# amp-PA-UHF-TQP7M9106.net
KiCad netlist of a schematic drawn in EAGLE
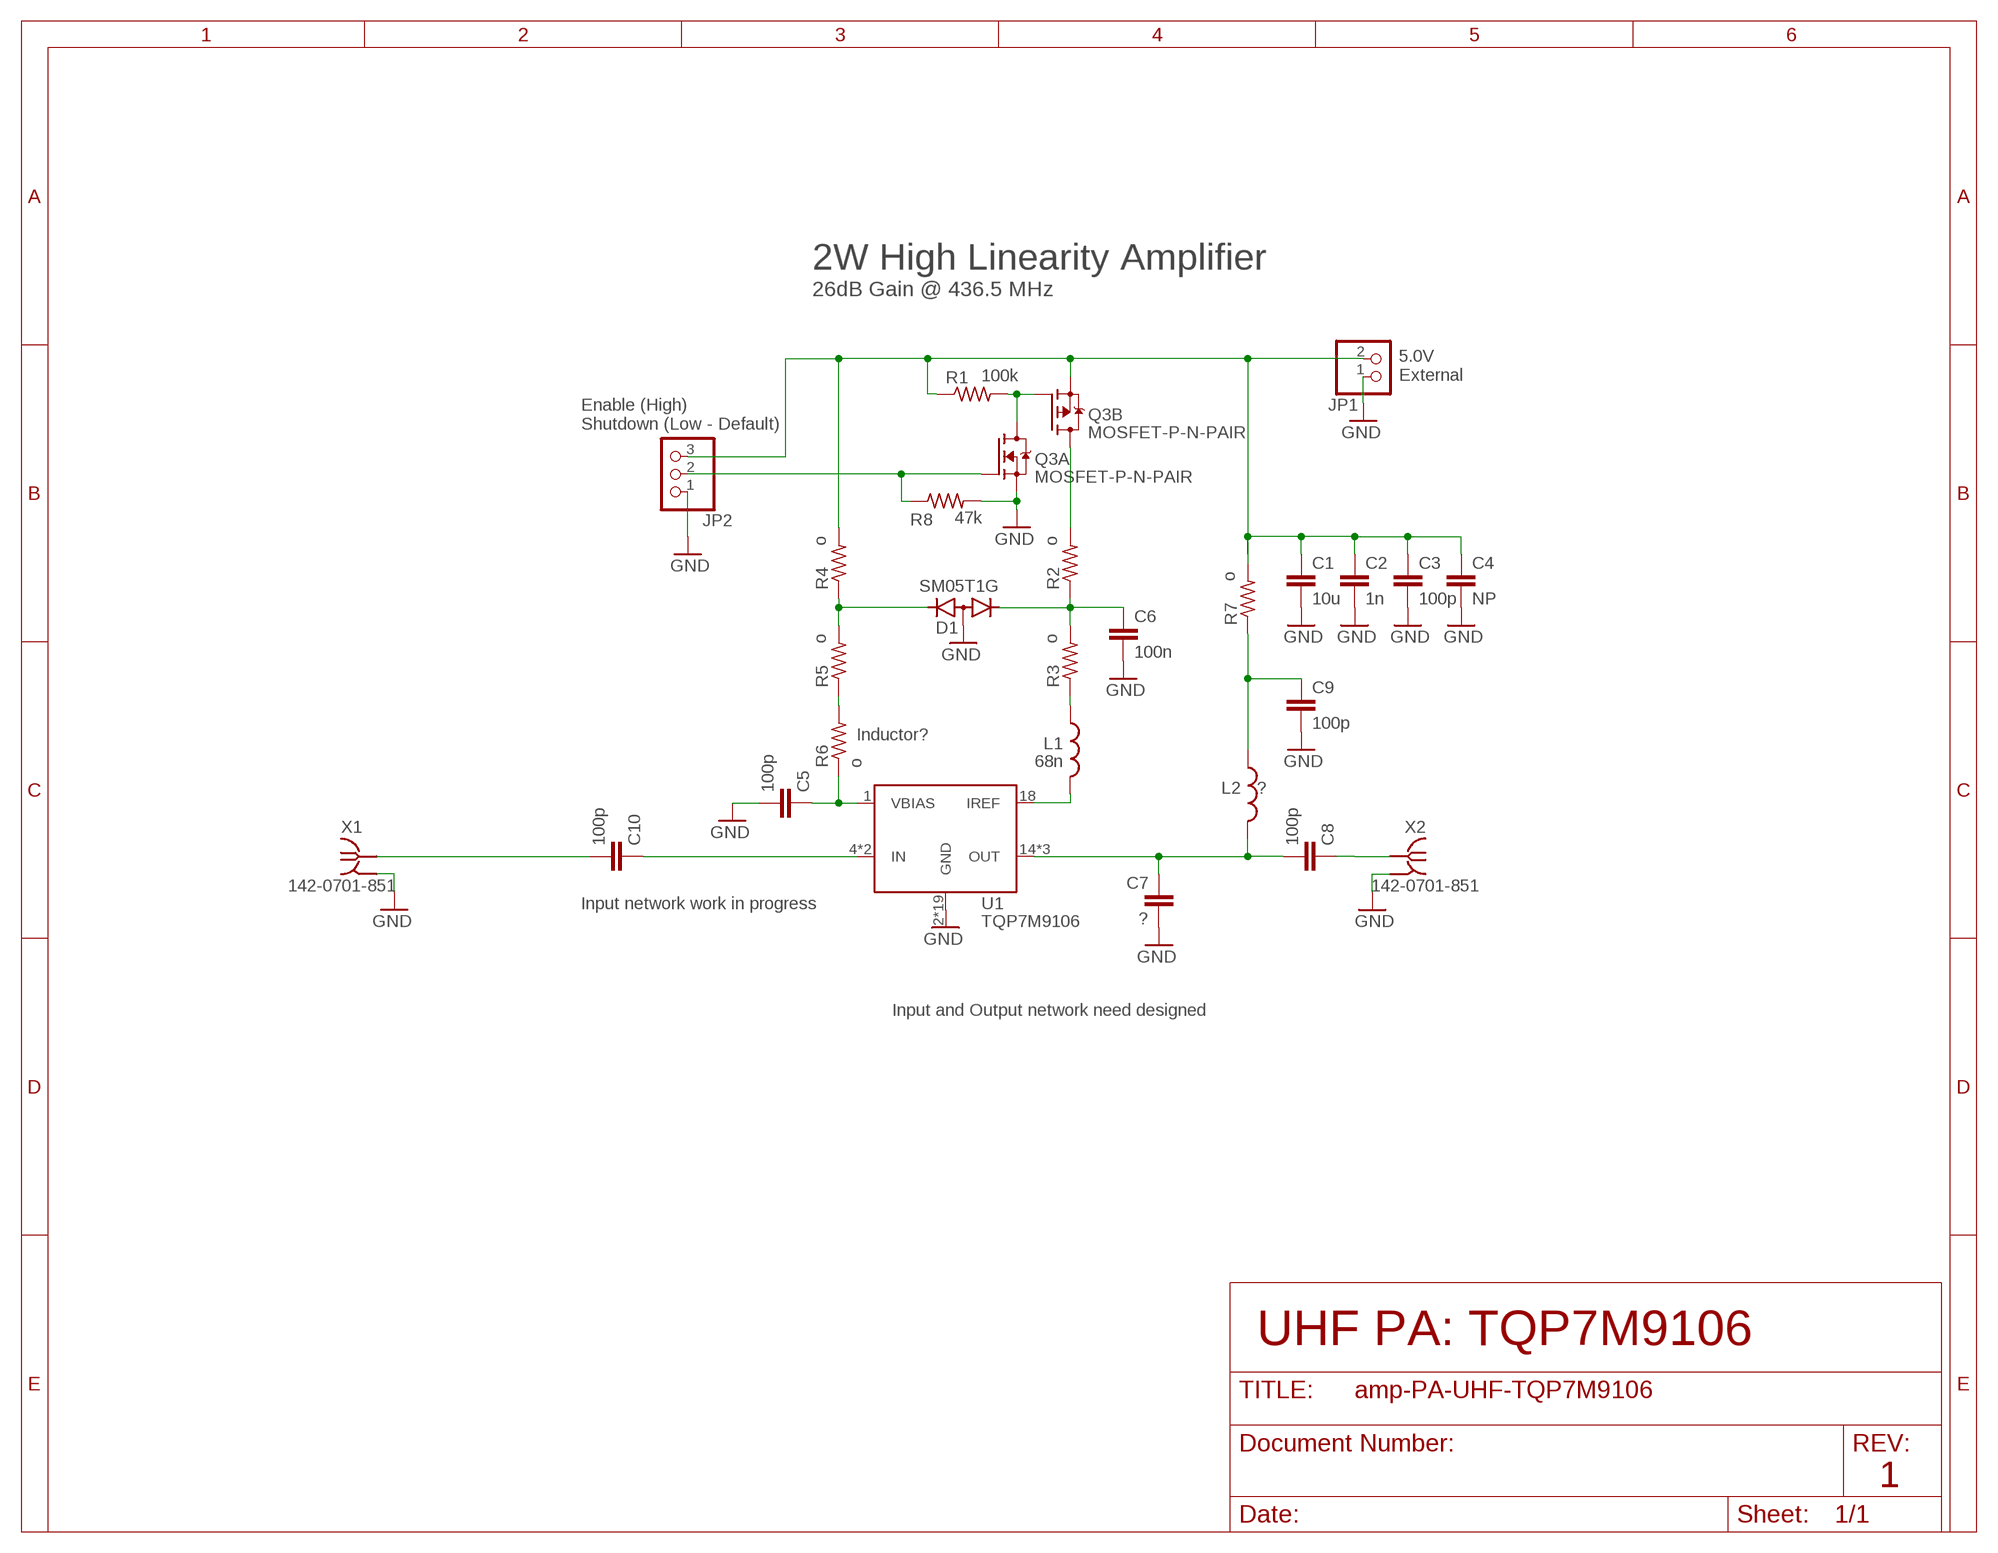
[diagram p0: schematic, sheet 1]

(export (version "E")
  (design (tool "Eeschema 10.0.6"))
  (components
    (comp (ref "C1")
      (value "10u")
      (footprint "eagle-import:.0603-B-NOSILK")
      (libsource (lib "eagle-import") (part "C-EU0603-B-NOSILK"))
    )
    (comp (ref "C2")
      (value "1n")
      (footprint "eagle-import:.0603-B-NOSILK")
      (libsource (lib "eagle-import") (part "C-EU0603-B-NOSILK"))
    )
    (comp (ref "C3")
      (value "100p")
      (footprint "eagle-import:.0603-B-NOSILK")
      (libsource (lib "eagle-import") (part "C-EU0603-B-NOSILK"))
    )
    (comp (ref "C4")
      (value "NP")
      (footprint "eagle-import:.0603-B-NOSILK")
      (libsource (lib "eagle-import") (part "C-EU0603-B-NOSILK"))
    )
    (comp (ref "C5")
      (value "100p")
      (footprint "eagle-import:.0603-B-NOSILK")
      (libsource (lib "eagle-import") (part "C-EU0603-B-NOSILK"))
    )
    (comp (ref "C6")
      (value "100n")
      (footprint "eagle-import:.0603-B-NOSILK")
      (libsource (lib "eagle-import") (part "C-EU0603-B-NOSILK"))
    )
    (comp (ref "C7")
      (value "?")
      (footprint "eagle-import:.0402-B-NOSILK")
      (libsource (lib "eagle-import") (part "C-EU0402-B-NOSILK"))
    )
    (comp (ref "C8")
      (value "100p")
      (footprint "eagle-import:.0402-B-NOSILK")
      (libsource (lib "eagle-import") (part "C-EU0402-B-NOSILK"))
    )
    (comp (ref "C9")
      (value "100p")
      (footprint "eagle-import:.0603-B-NOSILK")
      (libsource (lib "eagle-import") (part "C-EU0603-B-NOSILK"))
    )
    (comp (ref "C10")
      (value "100p")
      (footprint "eagle-import:.0402-B-NOSILK")
      (libsource (lib "eagle-import") (part "C-EU0402-B-NOSILK"))
    )
    (comp (ref "D1")
      (value "SM05T1G")
      (footprint "eagle-import:SOT23")
      (libsource (lib "eagle-import") (part "DIODE-2CA|ACSOT23"))
    )
    (comp (ref "JP1")
      (value "PINHD-1X2")
      (footprint "eagle-import:1X02")
      (libsource (lib "eagle-import") (part "PINHD-1X2"))
    )
    (comp (ref "JP2")
      (value "PINHD-1X3")
      (footprint "eagle-import:1X03")
      (libsource (lib "eagle-import") (part "PINHD-1X3"))
    )
    (comp (ref "L1")
      (value "68n")
      (footprint "eagle-import:.0603-B-NOSILK")
      (libsource (lib "eagle-import") (part "L-US0603-B-NOSILK"))
    )
    (comp (ref "L2")
      (value "?")
      (footprint "eagle-import:.0805-B-NOSILK")
      (libsource (lib "eagle-import") (part "L-US0805-B-NOSILK"))
    )
    (comp (ref "Q3")
      (value "MOSFET-P-N-PAIR")
      (footprint "eagle-import:SOT23-6")
      (libsource (lib "eagle-import") (part "MOSFET-P-N-PAIR"))
    )
    (comp (ref "R1")
      (value "100k")
      (footprint "eagle-import:.0402-B-NOSILK")
      (libsource (lib "eagle-import") (part "R-US_0402-B-NOSILK"))
    )
    (comp (ref "R2")
      (value "o")
      (footprint "eagle-import:.0805-B-NOSILK")
      (libsource (lib "eagle-import") (part "R-US_0805-B-NOSILK"))
    )
    (comp (ref "R3")
      (value "o")
      (footprint "eagle-import:.0603-B-NOSILK")
      (libsource (lib "eagle-import") (part "R-US_0603-B-NOSILK"))
    )
    (comp (ref "R4")
      (value "o")
      (footprint "eagle-import:.0805-B-NOSILK")
      (libsource (lib "eagle-import") (part "R-US_0805-B-NOSILK"))
    )
    (comp (ref "R5")
      (value "o")
      (footprint "eagle-import:.0603-B-NOSILK")
      (libsource (lib "eagle-import") (part "R-US_0603-B-NOSILK"))
    )
    (comp (ref "R6")
      (value "o")
      (footprint "eagle-import:.0603-B-NOSILK")
      (libsource (lib "eagle-import") (part "R-US_0603-B-NOSILK"))
    )
    (comp (ref "R7")
      (value "o")
      (footprint "eagle-import:.0805-B-NOSILK")
      (libsource (lib "eagle-import") (part "R-US_0805-B-NOSILK"))
    )
    (comp (ref "R8")
      (value "47k")
      (footprint "eagle-import:.0402-B-NOSILK")
      (libsource (lib "eagle-import") (part "R-US_0402-B-NOSILK"))
    )
    (comp (ref "U1")
      (value "TQP7M9106")
      (footprint "eagle-import:QFN24-4X4-WITH-PAD")
      (libsource (lib "eagle-import") (part "TQP7M9106"))
    )
    (comp (ref "X1")
      (value "142-0701-851")
      (footprint "eagle-import:142-0701-851")
      (libsource (lib "eagle-import") (part "142-0701-851"))
    )
    (comp (ref "X2")
      (value "142-0701-851")
      (footprint "eagle-import:142-0701-851")
      (libsource (lib "eagle-import") (part "142-0701-851"))
    )
  )
  (nets
    (net (code "1") (name "GND") (class "Default")
      (node (ref "C1") (pin "2") (pinfunction "2_2") (pintype "passive"))
      (node (ref "C2") (pin "2") (pinfunction "2_2") (pintype "passive"))
      (node (ref "C3") (pin "2") (pinfunction "2_2") (pintype "passive"))
      (node (ref "C4") (pin "2") (pinfunction "2_2") (pintype "passive"))
      (node (ref "C5") (pin "2") (pinfunction "2_2") (pintype "passive"))
      (node (ref "C6") (pin "2") (pinfunction "2_2") (pintype "passive"))
      (node (ref "C7") (pin "2") (pinfunction "2_2") (pintype "passive"))
      (node (ref "C9") (pin "2") (pinfunction "2_2") (pintype "passive"))
      (node (ref "D1") (pin "3") (pinfunction "A_3") (pintype "passive"))
      (node (ref "JP1") (pin "1") (pinfunction "1_1") (pintype "passive"))
      (node (ref "JP2") (pin "1") (pinfunction "1_1") (pintype "passive"))
      (node (ref "Q3") (pin "5") (pinfunction "S_5") (pintype "passive"))
      (node (ref "R8") (pin "2") (pinfunction "2_2") (pintype "passive"))
      (node (ref "U1") (pin "10") (pinfunction "GND_10") (pintype "power_in"))
      (node (ref "U1") (pin "11") (pinfunction "GND_11") (pintype "power_in"))
      (node (ref "U1") (pin "12") (pinfunction "GND_12") (pintype "power_in"))
      (node (ref "U1") (pin "13") (pinfunction "GND_13") (pintype "power_in"))
      (node (ref "U1") (pin "17") (pinfunction "GND_17") (pintype "power_in"))
      (node (ref "U1") (pin "19") (pinfunction "GND_19") (pintype "power_in"))
      (node (ref "U1") (pin "2") (pinfunction "GND_2") (pintype "power_in"))
      (node (ref "U1") (pin "20") (pinfunction "GND_20") (pintype "power_in"))
      (node (ref "U1") (pin "21") (pinfunction "GND_21") (pintype "power_in"))
      (node (ref "U1") (pin "22") (pinfunction "GND_22") (pintype "power_in"))
      (node (ref "U1") (pin "23") (pinfunction "GND_23") (pintype "power_in"))
      (node (ref "U1") (pin "24") (pinfunction "GND_24") (pintype "power_in"))
      (node (ref "U1") (pin "3") (pinfunction "GND_3") (pintype "power_in"))
      (node (ref "U1") (pin "6") (pinfunction "GND_6") (pintype "power_in"))
      (node (ref "U1") (pin "7") (pinfunction "GND_7") (pintype "power_in"))
      (node (ref "U1") (pin "8") (pinfunction "GND_8") (pintype "power_in"))
      (node (ref "U1") (pin "9") (pinfunction "GND_9") (pintype "power_in"))
      (node (ref "U1") (pin "BPAD") (pinfunction "GND_BPAD") (pintype "power_in"))
      (node (ref "U1") (pin "TPAD") (pinfunction "GND_TPAD") (pintype "power_in"))
      (node (ref "X1") (pin "GND1") (pinfunction "GND_GND1") (pintype "bidirectional"))
      (node (ref "X1") (pin "GND2") (pinfunction "GND_GND2") (pintype "bidirectional"))
      (node (ref "X1") (pin "GND3") (pinfunction "GND_GND3") (pintype "bidirectional"))
      (node (ref "X1") (pin "GND4") (pinfunction "GND_GND4") (pintype "bidirectional"))
      (node (ref "X2") (pin "GND1") (pinfunction "GND_GND1") (pintype "bidirectional"))
      (node (ref "X2") (pin "GND2") (pinfunction "GND_GND2") (pintype "bidirectional"))
      (node (ref "X2") (pin "GND3") (pinfunction "GND_GND3") (pintype "bidirectional"))
      (node (ref "X2") (pin "GND4") (pinfunction "GND_GND4") (pintype "bidirectional"))
    )
    (net (code "2") (name "Net-(C7-Pad1)") (class "Default")
      (node (ref "C7") (pin "1") (pinfunction "1_1") (pintype "passive"))
      (node (ref "C8") (pin "2") (pinfunction "2_2") (pintype "passive"))
      (node (ref "L2") (pin "2") (pinfunction "2_2") (pintype "passive"))
      (node (ref "U1") (pin "14") (pinfunction "OUT_14") (pintype "output"))
      (node (ref "U1") (pin "15") (pinfunction "OUT_15") (pintype "output"))
      (node (ref "U1") (pin "16") (pinfunction "OUT_16") (pintype "output"))
    )
    (net (code "3") (name "Net-(C9-Pad1)") (class "Default")
      (node (ref "C9") (pin "1") (pinfunction "1_1") (pintype "passive"))
      (node (ref "L2") (pin "1") (pinfunction "1_1") (pintype "passive"))
      (node (ref "R7") (pin "1") (pinfunction "1_1") (pintype "passive"))
    )
    (net (code "4") (name "Net-(C10-Pad1)") (class "Default")
      (node (ref "C10") (pin "1") (pinfunction "1_1") (pintype "passive"))
      (node (ref "U1") (pin "4") (pinfunction "IN_4") (pintype "input"))
      (node (ref "U1") (pin "5") (pinfunction "IN_5") (pintype "input"))
    )
    (net (code "5") (name "Net-(D1-K1)") (class "Default")
      (node (ref "C6") (pin "1") (pinfunction "1_1") (pintype "passive"))
      (node (ref "D1") (pin "1") (pinfunction "K1_1") (pintype "passive"))
      (node (ref "R2") (pin "1") (pinfunction "1_1") (pintype "passive"))
      (node (ref "R3") (pin "2") (pinfunction "2_2") (pintype "passive"))
    )
    (net (code "6") (name "Net-(D1-K2)") (class "Default")
      (node (ref "D1") (pin "2") (pinfunction "K2_2") (pintype "passive"))
      (node (ref "R4") (pin "1") (pinfunction "1_1") (pintype "passive"))
      (node (ref "R5") (pin "2") (pinfunction "2_2") (pintype "passive"))
    )
    (net (code "7") (name "Net-(L1-Pad1)") (class "Default")
      (node (ref "L1") (pin "1") (pinfunction "1_1") (pintype "passive"))
      (node (ref "R3") (pin "1") (pinfunction "1_1") (pintype "passive"))
    )
    (net (code "8") (name "Net-(Q3A-D)") (class "Default")
      (node (ref "Q3") (pin "3") (pinfunction "G_3") (pintype "passive"))
      (node (ref "Q3") (pin "6") (pinfunction "D_6") (pintype "passive"))
      (node (ref "R1") (pin "2") (pinfunction "2_2") (pintype "passive"))
    )
    (net (code "9") (name "Net-(Q3A-G)") (class "Default")
      (node (ref "JP2") (pin "2") (pinfunction "2_2") (pintype "passive"))
      (node (ref "Q3") (pin "1") (pinfunction "G_1") (pintype "passive"))
      (node (ref "R8") (pin "1") (pinfunction "1_1") (pintype "passive"))
    )
    (net (code "10") (name "Net-(Q3B-D)") (class "Default")
      (node (ref "Q3") (pin "4") (pinfunction "D_4") (pintype "passive"))
      (node (ref "R2") (pin "2") (pinfunction "2_2") (pintype "passive"))
    )
    (net (code "11") (name "Net-(Q3B-S)") (class "Default")
      (node (ref "C1") (pin "1") (pinfunction "1_1") (pintype "passive"))
      (node (ref "C2") (pin "1") (pinfunction "1_1") (pintype "passive"))
      (node (ref "C3") (pin "1") (pinfunction "1_1") (pintype "passive"))
      (node (ref "C4") (pin "1") (pinfunction "1_1") (pintype "passive"))
      (node (ref "JP1") (pin "2") (pinfunction "2_2") (pintype "passive"))
      (node (ref "JP2") (pin "3") (pinfunction "3_3") (pintype "passive"))
      (node (ref "Q3") (pin "2") (pinfunction "S_2") (pintype "passive"))
      (node (ref "R1") (pin "1") (pinfunction "1_1") (pintype "passive"))
      (node (ref "R4") (pin "2") (pinfunction "2_2") (pintype "passive"))
      (node (ref "R7") (pin "2") (pinfunction "2_2") (pintype "passive"))
    )
    (net (code "12") (name "Net-(R5-Pad1)") (class "Default")
      (node (ref "R5") (pin "1") (pinfunction "1_1") (pintype "passive"))
      (node (ref "R6") (pin "2") (pinfunction "2_2") (pintype "passive"))
    )
    (net (code "13") (name "Net-(U1-IREF)") (class "Default")
      (node (ref "L1") (pin "2") (pinfunction "2_2") (pintype "passive"))
      (node (ref "U1") (pin "18") (pinfunction "IREF_18") (pintype "power_in"))
    )
    (net (code "14") (name "Net-(U1-VBIAS)") (class "Default")
      (node (ref "C5") (pin "1") (pinfunction "1_1") (pintype "passive"))
      (node (ref "R6") (pin "1") (pinfunction "1_1") (pintype "passive"))
      (node (ref "U1") (pin "1") (pinfunction "VBIAS_1") (pintype "power_in"))
    )
    (net (code "15") (name "Net-(X1-RF)") (class "Default")
      (node (ref "C10") (pin "2") (pinfunction "2_2") (pintype "passive"))
      (node (ref "X1") (pin "RF1") (pinfunction "RF_RF1") (pintype "bidirectional"))
    )
    (net (code "16") (name "Net-(X2-RF)") (class "Default")
      (node (ref "C8") (pin "1") (pinfunction "1_1") (pintype "passive"))
      (node (ref "X2") (pin "RF1") (pinfunction "RF_RF1") (pintype "bidirectional"))
    )
  )
)
